# carChargeChannel.net
KiCad netlist of a schematic drawn in EAGLE
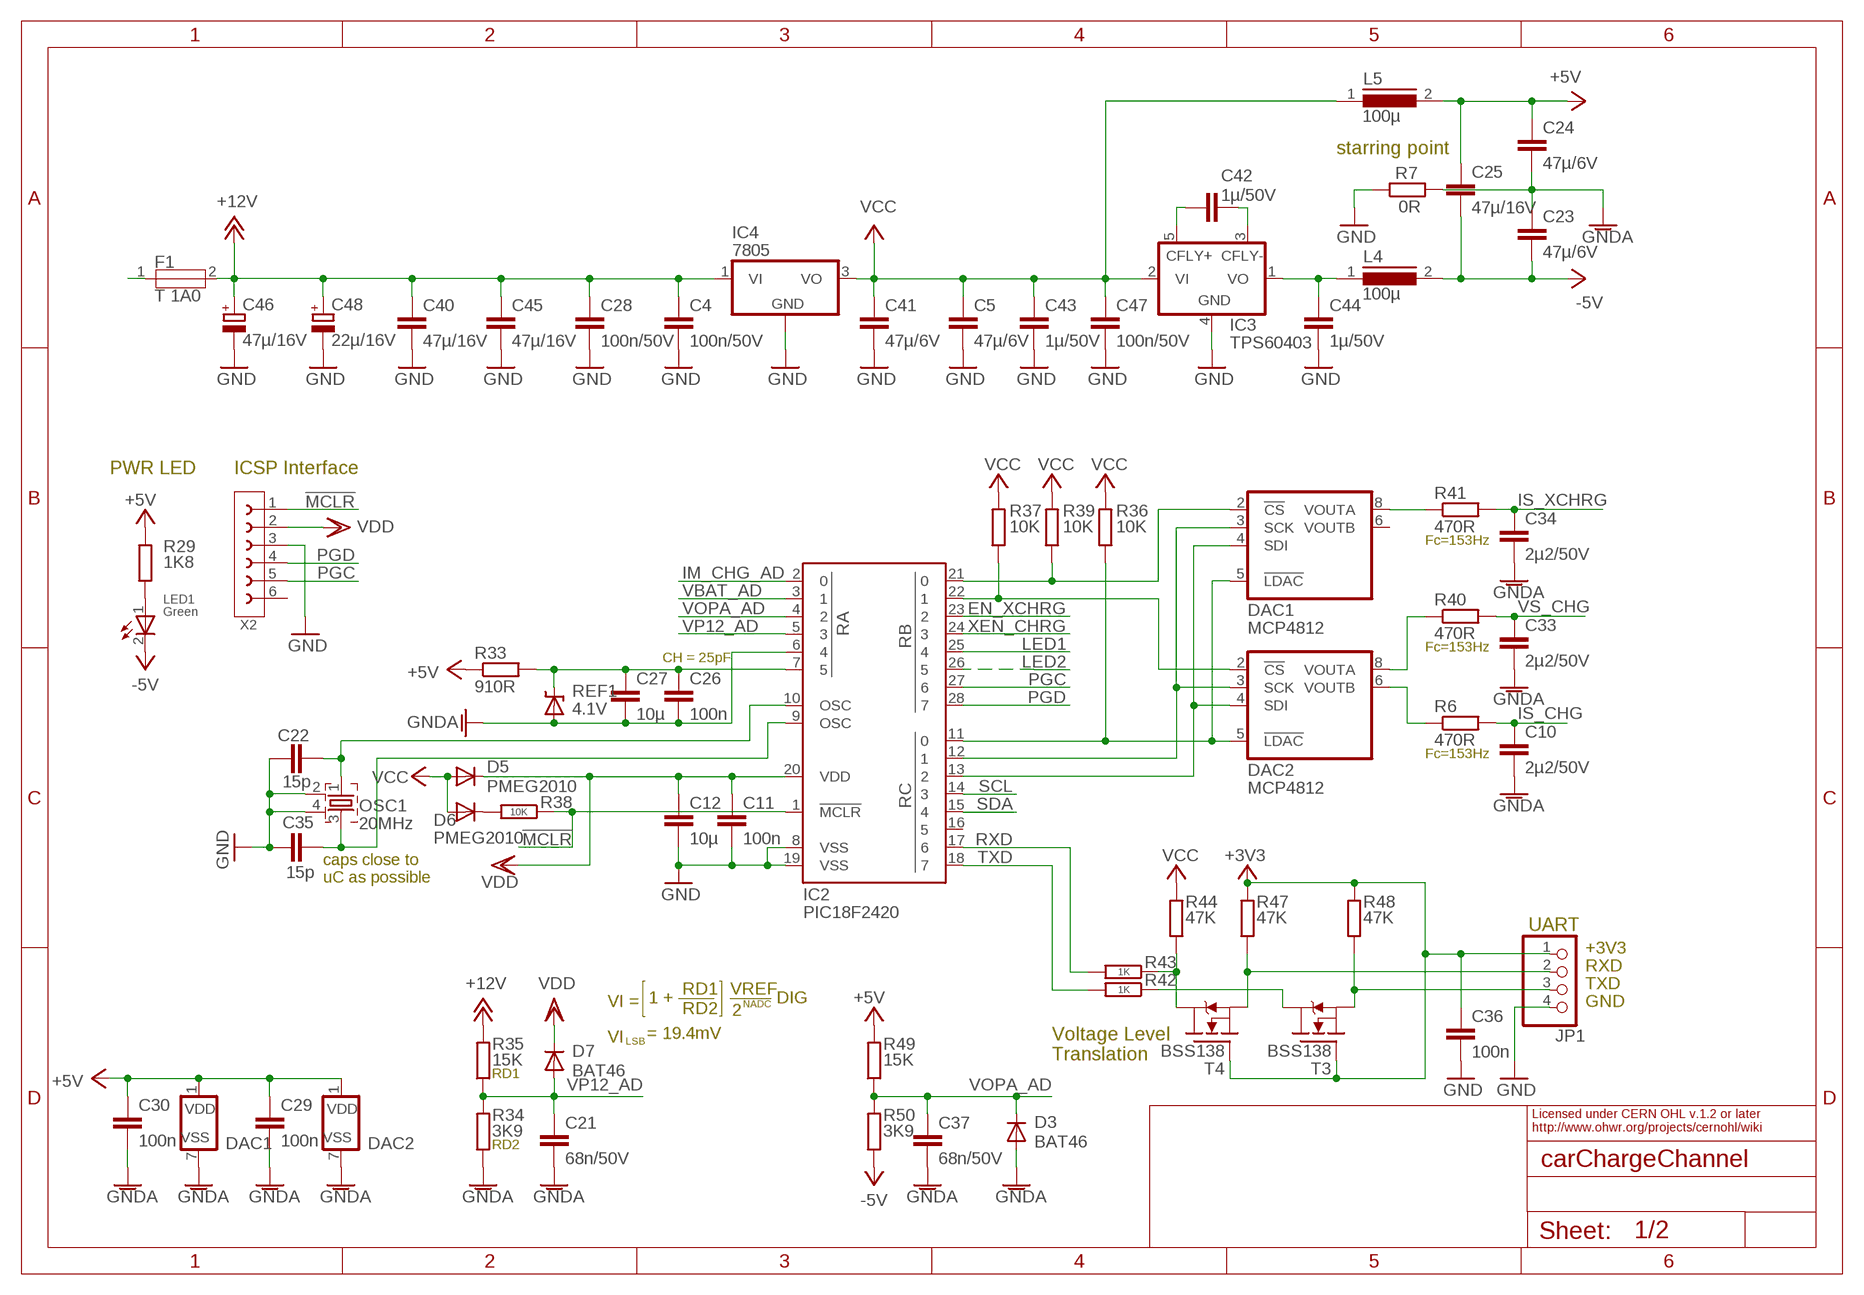
[diagram p0: schematic, sheet 1]
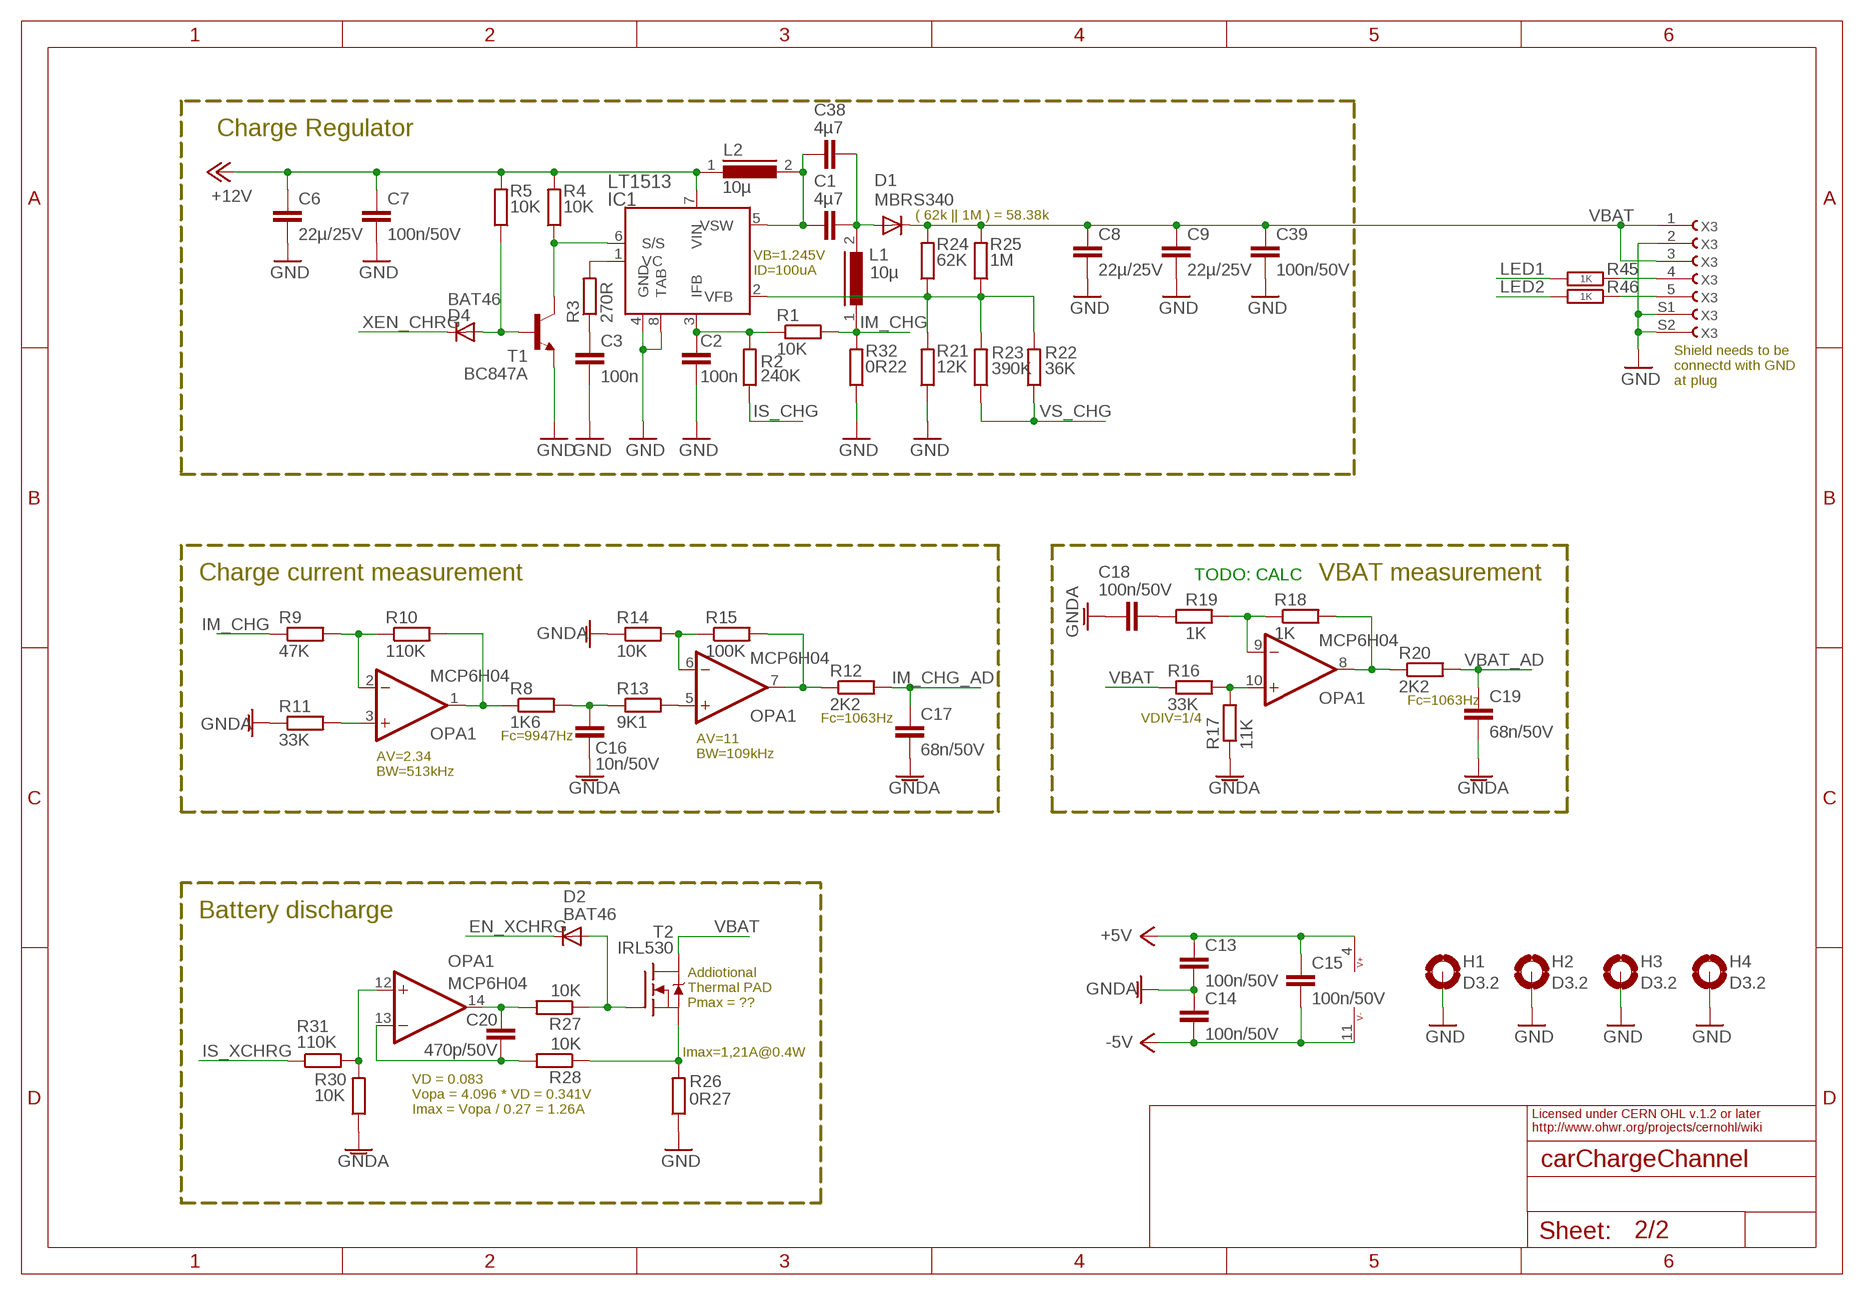
[diagram p1: schematic, sheet 2]

(export (version "E")
  (design (tool "Eeschema 10.0.6"))
  (components
    (comp (ref "C4")
      (value "100n/50V")
      (footprint "eagle-import:1206")
      (libsource (lib "eagle-import") (part "X7R-1206-100000P"))
    )
    (comp (ref "C5")
      (value "47µ/6V")
      (footprint "eagle-import:1206")
      (libsource (lib "eagle-import") (part "X5R-1206-47000000P"))
    )
    (comp (ref "C10")
      (value "2µ2/50V")
      (footprint "eagle-import:1206")
      (libsource (lib "eagle-import") (part "X7R-1206-2200000P"))
    )
    (comp (ref "C11")
      (value "100n")
      (footprint "eagle-import:1206")
      (libsource (lib "eagle-import") (part "X7R-1206-100000P"))
    )
    (comp (ref "C12")
      (value "10µ")
      (footprint "eagle-import:1206")
      (libsource (lib "eagle-import") (part "X7R-1206-10000000P"))
    )
    (comp (ref "C21")
      (value "68n/50V")
      (footprint "eagle-import:1206")
      (libsource (lib "eagle-import") (part "X7R-1206-68000P"))
    )
    (comp (ref "C22")
      (value "15p")
      (footprint "eagle-import:1206")
      (libsource (lib "eagle-import") (part "NP0-1206-15P"))
    )
    (comp (ref "C23")
      (value "47µ/6V")
      (footprint "eagle-import:1206")
      (libsource (lib "eagle-import") (part "X5R-1206-47000000P"))
    )
    (comp (ref "C24")
      (value "47µ/6V")
      (footprint "eagle-import:1206")
      (libsource (lib "eagle-import") (part "X5R-1206-47000000P"))
    )
    (comp (ref "C25")
      (value "47µ/16V")
      (footprint "eagle-import:1210")
      (libsource (lib "eagle-import") (part "X5R-1210-47000000P"))
    )
    (comp (ref "C26")
      (value "100n")
      (footprint "eagle-import:1206")
      (libsource (lib "eagle-import") (part "X7R-1206-100000P"))
    )
    (comp (ref "C27")
      (value "10µ")
      (footprint "eagle-import:1206")
      (libsource (lib "eagle-import") (part "X7R-1206-10000000P"))
    )
    (comp (ref "C28")
      (value "100n/50V")
      (footprint "eagle-import:1206")
      (libsource (lib "eagle-import") (part "X7R-1206-100000P"))
    )
    (comp (ref "C29")
      (value "100n")
      (footprint "eagle-import:1206")
      (libsource (lib "eagle-import") (part "X7R-1206-100000P"))
    )
    (comp (ref "C30")
      (value "100n")
      (footprint "eagle-import:1206")
      (libsource (lib "eagle-import") (part "X7R-1206-100000P"))
    )
    (comp (ref "C33")
      (value "2µ2/50V")
      (footprint "eagle-import:1206")
      (libsource (lib "eagle-import") (part "X7R-1206-2200000P"))
    )
    (comp (ref "C34")
      (value "2µ2/50V")
      (footprint "eagle-import:1206")
      (libsource (lib "eagle-import") (part "X7R-1206-2200000P"))
    )
    (comp (ref "C35")
      (value "15p")
      (footprint "eagle-import:1206")
      (libsource (lib "eagle-import") (part "NP0-1206-15P"))
    )
    (comp (ref "C36")
      (value "100n")
      (footprint "eagle-import:1206")
      (libsource (lib "eagle-import") (part "X7R-1206-100000P"))
    )
    (comp (ref "C37")
      (value "68n/50V")
      (footprint "eagle-import:1206")
      (libsource (lib "eagle-import") (part "X7R-1206-68000P"))
    )
    (comp (ref "C40")
      (value "47µ/16V")
      (footprint "eagle-import:1210")
      (libsource (lib "eagle-import") (part "X5R-1210-47000000P"))
    )
    (comp (ref "C41")
      (value "47µ/6V")
      (footprint "eagle-import:1206")
      (libsource (lib "eagle-import") (part "X5R-1206-47000000P"))
    )
    (comp (ref "C42")
      (value "1µ/50V")
      (footprint "eagle-import:1206")
      (libsource (lib "eagle-import") (part "X7R-1206-1000000P"))
    )
    (comp (ref "C43")
      (value "1µ/50V")
      (footprint "eagle-import:1206")
      (libsource (lib "eagle-import") (part "X7R-1206-1000000P"))
    )
    (comp (ref "C44")
      (value "1µ/50V")
      (footprint "eagle-import:1206")
      (libsource (lib "eagle-import") (part "X7R-1206-1000000P"))
    )
    (comp (ref "C45")
      (value "47µ/16V")
      (footprint "eagle-import:1210")
      (libsource (lib "eagle-import") (part "X5R-1210-47000000P"))
    )
    (comp (ref "C46")
      (value "47µ/16V")
      (footprint "eagle-import:PANC")
      (libsource (lib "eagle-import") (part "AEC-C-47U-16V"))
    )
    (comp (ref "C47")
      (value "100n/50V")
      (footprint "eagle-import:1206")
      (libsource (lib "eagle-import") (part "X7R-1206-100000P"))
    )
    (comp (ref "C48")
      (value "22µ/16V")
      (footprint "eagle-import:PANB")
      (libsource (lib "eagle-import") (part "AEC-B-22U-16V"))
    )
    (comp (ref "D3")
      (value "BAT46")
      (footprint "eagle-import:SOD123")
      (libsource (lib "eagle-import") (part "BAT46W"))
    )
    (comp (ref "D5")
      (value "PMEG2010")
      (footprint "eagle-import:SOD323")
      (libsource (lib "eagle-import") (part "PMEGXX10BEA-20V"))
    )
    (comp (ref "D6")
      (value "PMEG2010")
      (footprint "eagle-import:SOD323")
      (libsource (lib "eagle-import") (part "PMEGXX10BEA-20V"))
    )
    (comp (ref "D7")
      (value "BAT46")
      (footprint "eagle-import:SOD123")
      (libsource (lib "eagle-import") (part "BAT46W"))
    )
    (comp (ref "DAC1")
      (value "MCP4812")
      (footprint "eagle-import:MSOP8")
      (libsource (lib "eagle-import") (part "MCP48-E/MS12"))
    )
    (comp (ref "DAC2")
      (value "MCP4812")
      (footprint "eagle-import:MSOP8")
      (libsource (lib "eagle-import") (part "MCP48-E/MS12"))
    )
    (comp (ref "F1")
      (value "T 1A0")
      (footprint "eagle-import:OMT125")
      (libsource (lib "eagle-import") (part "OMT-125V-T1A0"))
    )
    (comp (ref "IC2")
      (value "PIC18F2420")
      (footprint "eagle-import:SOIC28-7.62")
      (libsource (lib "eagle-import") (part "PIC18F2420/SO"))
    )
    (comp (ref "IC3")
      (value "TPS60403")
      (footprint "eagle-import:SOT23-5")
      (libsource (lib "eagle-import") (part "TPS6040DBVT3"))
    )
    (comp (ref "IC4")
      (value "7805")
      (footprint "eagle-import:TO263")
      (libsource (lib "eagle-import") (part "MC78D2T05"))
    )
    (comp (ref "JP1")
      (value "PINHD-1X4")
      (footprint "eagle-import:1X04")
      (libsource (lib "eagle-import") (part "PINHD-1X4"))
    )
    (comp (ref "L4")
      (value "100µ")
      (footprint "eagle-import:1210")
      (libsource (lib "eagle-import") (part "LQH3C101K"))
    )
    (comp (ref "L5")
      (value "100µ")
      (footprint "eagle-import:1210")
      (libsource (lib "eagle-import") (part "LQH3C101K"))
    )
    (comp (ref "LED1")
      (value "Green")
      (footprint "eagle-import:LED3216")
      (libsource (lib "eagle-import") (part "LEDMONO-KP3216-GREEN"))
    )
    (comp (ref "OSC1")
      (value "20MHz")
      (footprint "eagle-import:MT")
      (libsource (lib "eagle-import") (part "MT-20000"))
    )
    (comp (ref "R6")
      (value "470R")
      (footprint "eagle-import:1206")
      (libsource (lib "eagle-import") (part "RC1206-470"))
    )
    (comp (ref "R7")
      (value "0R")
      (footprint "eagle-import:1206")
      (libsource (lib "eagle-import") (part "R1206-1%-0.0"))
    )
    (comp (ref "R29")
      (value "1K8")
      (footprint "eagle-import:1206")
      (libsource (lib "eagle-import") (part "R1206-1%-1800"))
    )
    (comp (ref "R33")
      (value "910R")
      (footprint "eagle-import:1206")
      (libsource (lib "eagle-import") (part "R1206-1%-910"))
    )
    (comp (ref "R34")
      (value "3K9")
      (footprint "eagle-import:1206")
      (libsource (lib "eagle-import") (part "R1206-1%-3900"))
    )
    (comp (ref "R35")
      (value "15K")
      (footprint "eagle-import:1206")
      (libsource (lib "eagle-import") (part "R1206-1%-15000"))
    )
    (comp (ref "R36")
      (value "10K")
      (footprint "eagle-import:1206")
      (libsource (lib "eagle-import") (part "R1206-1%-10000"))
    )
    (comp (ref "R37")
      (value "10K")
      (footprint "eagle-import:1206")
      (libsource (lib "eagle-import") (part "R1206-1%-10000"))
    )
    (comp (ref "R38")
      (value "10K")
      (footprint "eagle-import:1206")
      (libsource (lib "eagle-import") (part "R1206-1%-10000"))
    )
    (comp (ref "R39")
      (value "10K")
      (footprint "eagle-import:1206")
      (libsource (lib "eagle-import") (part "R1206-1%-10000"))
    )
    (comp (ref "R40")
      (value "470R")
      (footprint "eagle-import:1206")
      (libsource (lib "eagle-import") (part "RC1206-470"))
    )
    (comp (ref "R41")
      (value "470R")
      (footprint "eagle-import:1206")
      (libsource (lib "eagle-import") (part "RC1206-470"))
    )
    (comp (ref "R42")
      (value "1K")
      (footprint "eagle-import:1206")
      (libsource (lib "eagle-import") (part "R1206-1%-1000"))
    )
    (comp (ref "R43")
      (value "1K")
      (footprint "eagle-import:1206")
      (libsource (lib "eagle-import") (part "R1206-1%-1000"))
    )
    (comp (ref "R44")
      (value "47K")
      (footprint "eagle-import:1206")
      (libsource (lib "eagle-import") (part "R1206-1%-47000"))
    )
    (comp (ref "R47")
      (value "47K")
      (footprint "eagle-import:1206")
      (libsource (lib "eagle-import") (part "R1206-1%-47000"))
    )
    (comp (ref "R48")
      (value "47K")
      (footprint "eagle-import:1206")
      (libsource (lib "eagle-import") (part "R1206-1%-47000"))
    )
    (comp (ref "R49")
      (value "15K")
      (footprint "eagle-import:1206")
      (libsource (lib "eagle-import") (part "R1206-1%-15000"))
    )
    (comp (ref "R50")
      (value "3K9")
      (footprint "eagle-import:1206")
      (libsource (lib "eagle-import") (part "R1206-1%-3900"))
    )
    (comp (ref "REF1")
      (value "4.1V")
      (footprint "eagle-import:SOT23")
      (libsource (lib "eagle-import") (part "LM4040-MF03A-4.1V"))
    )
    (comp (ref "T3")
      (value "BSS138")
      (footprint "eagle-import:SOT23")
      (libsource (lib "eagle-import") (part "BSS138"))
    )
    (comp (ref "T4")
      (value "BSS138")
      (footprint "eagle-import:SOT23")
      (libsource (lib "eagle-import") (part "BSS138"))
    )
    (comp (ref "X2")
      (value "2X3")
      (footprint "eagle-import:BOXHD-06-2.54-S")
      (libsource (lib "eagle-import") (part "BOXHD-06-2.54-S"))
    )
    (comp (ref "C1")
      (value "4µ7")
      (footprint "eagle-import:1206")
      (libsource (lib "eagle-import") (part "X7R-1206-4700000P"))
    )
    (comp (ref "C2")
      (value "100n")
      (footprint "eagle-import:1206")
      (libsource (lib "eagle-import") (part "X7R-1206-100000P"))
    )
    (comp (ref "C3")
      (value "100n")
      (footprint "eagle-import:1206")
      (libsource (lib "eagle-import") (part "X7R-1206-100000P"))
    )
    (comp (ref "C6")
      (value "22µ/25V")
      (footprint "eagle-import:1210")
      (libsource (lib "eagle-import") (part "X5R-1210-22000000P"))
    )
    (comp (ref "C7")
      (value "100n/50V")
      (footprint "eagle-import:1206")
      (libsource (lib "eagle-import") (part "X7R-1206-100000P"))
    )
    (comp (ref "C8")
      (value "22µ/25V")
      (footprint "eagle-import:1210")
      (libsource (lib "eagle-import") (part "X5R-1210-22000000P"))
    )
    (comp (ref "C9")
      (value "22µ/25V")
      (footprint "eagle-import:1210")
      (libsource (lib "eagle-import") (part "X5R-1210-22000000P"))
    )
    (comp (ref "C13")
      (value "100n/50V")
      (footprint "eagle-import:1206")
      (libsource (lib "eagle-import") (part "X7R-1206-100000P"))
    )
    (comp (ref "C14")
      (value "100n/50V")
      (footprint "eagle-import:1206")
      (libsource (lib "eagle-import") (part "X7R-1206-100000P"))
    )
    (comp (ref "C15")
      (value "100n/50V")
      (footprint "eagle-import:1206")
      (libsource (lib "eagle-import") (part "X7R-1206-100000P"))
    )
    (comp (ref "C16")
      (value "10n/50V")
      (footprint "eagle-import:1206")
      (libsource (lib "eagle-import") (part "X7R-1206-10000P"))
    )
    (comp (ref "C17")
      (value "68n/50V")
      (footprint "eagle-import:1206")
      (libsource (lib "eagle-import") (part "X7R-1206-68000P"))
    )
    (comp (ref "C18")
      (value "100n/50V")
      (footprint "eagle-import:1206")
      (libsource (lib "eagle-import") (part "X7R-1206-100000P"))
    )
    (comp (ref "C19")
      (value "68n/50V")
      (footprint "eagle-import:1206")
      (libsource (lib "eagle-import") (part "X7R-1206-68000P"))
    )
    (comp (ref "C20")
      (value "470p/50V")
      (footprint "eagle-import:1206")
      (libsource (lib "eagle-import") (part "NP0-1206-470P"))
    )
    (comp (ref "C38")
      (value "4µ7")
      (footprint "eagle-import:1206")
      (libsource (lib "eagle-import") (part "X7R-1206-4700000P"))
    )
    (comp (ref "C39")
      (value "100n/50V")
      (footprint "eagle-import:1206")
      (libsource (lib "eagle-import") (part "X7R-1206-100000P"))
    )
    (comp (ref "D1")
      (value "MBRS340")
      (footprint "eagle-import:DO214AB")
      (libsource (lib "eagle-import") (part "MBRS340"))
    )
    (comp (ref "D2")
      (value "BAT46")
      (footprint "eagle-import:SOD123")
      (libsource (lib "eagle-import") (part "BAT46W"))
    )
    (comp (ref "D4")
      (value "BAT46")
      (footprint "eagle-import:SOD123")
      (libsource (lib "eagle-import") (part "BAT46W"))
    )
    (comp (ref "H1")
      (value "D3.2")
      (footprint "eagle-import:3,2-PAD")
      (libsource (lib "eagle-import") (part "MOUNT-PAD-ROUND3.2"))
    )
    (comp (ref "H2")
      (value "D3.2")
      (footprint "eagle-import:3,2-PAD")
      (libsource (lib "eagle-import") (part "MOUNT-PAD-ROUND3.2"))
    )
    (comp (ref "H3")
      (value "D3.2")
      (footprint "eagle-import:3,2-PAD")
      (libsource (lib "eagle-import") (part "MOUNT-PAD-ROUND3.2"))
    )
    (comp (ref "H4")
      (value "D3.2")
      (footprint "eagle-import:3,2-PAD")
      (libsource (lib "eagle-import") (part "MOUNT-PAD-ROUND3.2"))
    )
    (comp (ref "IC1")
      (value "LT1513")
      (footprint "eagle-import:TO263-7")
      (libsource (lib "eagle-import") (part "LT1513CR"))
    )
    (comp (ref "L1")
      (value "10µ")
      (footprint "eagle-import:DR74")
      (libsource (lib "eagle-import") (part "DR--7410U"))
    )
    (comp (ref "L2")
      (value "10µ")
      (footprint "eagle-import:DR74")
      (libsource (lib "eagle-import") (part "DR--7410U"))
    )
    (comp (ref "OPA1")
      (value "MCP6H04")
      (footprint "eagle-import:SOIC14")
      (libsource (lib "eagle-import") (part "MCP6H04"))
    )
    (comp (ref "R1")
      (value "10K")
      (footprint "eagle-import:1206")
      (libsource (lib "eagle-import") (part "R1206-1%-10000"))
    )
    (comp (ref "R2")
      (value "240K")
      (footprint "eagle-import:1206")
      (libsource (lib "eagle-import") (part "R1206-1%-240000"))
    )
    (comp (ref "R3")
      (value "270R")
      (footprint "eagle-import:1206")
      (libsource (lib "eagle-import") (part "R1206-1%-270"))
    )
    (comp (ref "R4")
      (value "10K")
      (footprint "eagle-import:1206")
      (libsource (lib "eagle-import") (part "R1206-1%-10000"))
    )
    (comp (ref "R5")
      (value "10K")
      (footprint "eagle-import:1206")
      (libsource (lib "eagle-import") (part "R1206-1%-10000"))
    )
    (comp (ref "R8")
      (value "1K6")
      (footprint "eagle-import:1206")
      (libsource (lib "eagle-import") (part "R1206-1%-1600"))
    )
    (comp (ref "R9")
      (value "47K")
      (footprint "eagle-import:1206")
      (libsource (lib "eagle-import") (part "R1206-1%-47000"))
    )
    (comp (ref "R10")
      (value "110K")
      (footprint "eagle-import:1206")
      (libsource (lib "eagle-import") (part "R1206-1%-110000"))
    )
    (comp (ref "R11")
      (value "33K")
      (footprint "eagle-import:1206")
      (libsource (lib "eagle-import") (part "R1206-1%-33000"))
    )
    (comp (ref "R12")
      (value "2K2")
      (footprint "eagle-import:1206")
      (libsource (lib "eagle-import") (part "R1206-1%-2200"))
    )
    (comp (ref "R13")
      (value "9K1")
      (footprint "eagle-import:1206")
      (libsource (lib "eagle-import") (part "R1206-1%-9100"))
    )
    (comp (ref "R14")
      (value "10K")
      (footprint "eagle-import:1206")
      (libsource (lib "eagle-import") (part "R1206-1%-10000"))
    )
    (comp (ref "R15")
      (value "100K")
      (footprint "eagle-import:1206")
      (libsource (lib "eagle-import") (part "R1206-1%-100000"))
    )
    (comp (ref "R16")
      (value "33K")
      (footprint "eagle-import:1206")
      (libsource (lib "eagle-import") (part "R1206-1%-33000"))
    )
    (comp (ref "R17")
      (value "11K")
      (footprint "eagle-import:1206")
      (libsource (lib "eagle-import") (part "R1206-1%-11000"))
    )
    (comp (ref "R18")
      (value "1K")
      (footprint "eagle-import:1206")
      (libsource (lib "eagle-import") (part "R1206-1%-1000"))
    )
    (comp (ref "R19")
      (value "1K")
      (footprint "eagle-import:1206")
      (libsource (lib "eagle-import") (part "R1206-1%-1000"))
    )
    (comp (ref "R20")
      (value "2K2")
      (footprint "eagle-import:1206")
      (libsource (lib "eagle-import") (part "R1206-1%-2200"))
    )
    (comp (ref "R21")
      (value "12K")
      (footprint "eagle-import:1206")
      (libsource (lib "eagle-import") (part "R1206-1%-12000"))
    )
    (comp (ref "R22")
      (value "36K")
      (footprint "eagle-import:1206")
      (libsource (lib "eagle-import") (part "R1206-1%-36000"))
    )
    (comp (ref "R23")
      (value "390K")
      (footprint "eagle-import:1206")
      (libsource (lib "eagle-import") (part "R1206-1%-390000"))
    )
    (comp (ref "R24")
      (value "62K")
      (footprint "eagle-import:1206")
      (libsource (lib "eagle-import") (part "R1206-1%-62000"))
    )
    (comp (ref "R25")
      (value "1M")
      (footprint "eagle-import:1206")
      (libsource (lib "eagle-import") (part "R1206-1%-1000000"))
    )
    (comp (ref "R26")
      (value "0R27")
      (footprint "eagle-import:1206")
      (libsource (lib "eagle-import") (part "R1206-5%-0.27"))
    )
    (comp (ref "R27")
      (value "10K")
      (footprint "eagle-import:1206")
      (libsource (lib "eagle-import") (part "R1206-1%-10000"))
    )
    (comp (ref "R28")
      (value "10K")
      (footprint "eagle-import:1206")
      (libsource (lib "eagle-import") (part "R1206-1%-10000"))
    )
    (comp (ref "R30")
      (value "10K")
      (footprint "eagle-import:1206")
      (libsource (lib "eagle-import") (part "R1206-1%-10000"))
    )
    (comp (ref "R31")
      (value "110K")
      (footprint "eagle-import:1206")
      (libsource (lib "eagle-import") (part "R1206-1%-110000"))
    )
    (comp (ref "R32")
      (value "0R22")
      (footprint "eagle-import:1206")
      (libsource (lib "eagle-import") (part "R1206-1%-0.22"))
    )
    (comp (ref "R45")
      (value "1K")
      (footprint "eagle-import:1206")
      (libsource (lib "eagle-import") (part "R1206-1%-1000"))
    )
    (comp (ref "R46")
      (value "1K")
      (footprint "eagle-import:1206")
      (libsource (lib "eagle-import") (part "R1206-1%-1000"))
    )
    (comp (ref "T1")
      (value "BC847A")
      (footprint "eagle-import:SOT23")
      (libsource (lib "eagle-import") (part "BC847A"))
    )
    (comp (ref "T2")
      (value "IRL530")
      (footprint "eagle-import:TO263AB")
      (libsource (lib "eagle-import") (part "IRL530NS"))
    )
    (comp (ref "X3")
      (value "DIN5")
      (footprint "eagle-import:DIN5P")
      (libsource (lib "eagle-import") (part "MAB-5S"))
    )
  )
  (nets
    (net (code "1") (name "+3V3") (class "Default")
      (node (ref "C36") (pin "1") (pinfunction "1_1") (pintype "passive"))
      (node (ref "JP1") (pin "1") (pinfunction "1_1") (pintype "passive"))
      (node (ref "R47") (pin "2") (pinfunction "2_2") (pintype "passive"))
      (node (ref "R48") (pin "2") (pinfunction "2_2") (pintype "passive"))
      (node (ref "T3") (pin "1") (pinfunction "G_1") (pintype "bidirectional"))
      (node (ref "T4") (pin "1") (pinfunction "G_1") (pintype "bidirectional"))
    )
    (net (code "2") (name "+5V") (class "Default")
      (node (ref "C13") (pin "1") (pinfunction "1_1") (pintype "passive"))
      (node (ref "C15") (pin "1") (pinfunction "1_1") (pintype "passive"))
      (node (ref "C24") (pin "1") (pinfunction "1_1") (pintype "passive"))
      (node (ref "C25") (pin "1") (pinfunction "1_1") (pintype "passive"))
      (node (ref "C29") (pin "1") (pinfunction "1_1") (pintype "passive"))
      (node (ref "C30") (pin "1") (pinfunction "1_1") (pintype "passive"))
      (node (ref "DAC1") (pin "1") (pinfunction "VDD_1") (pintype "power_in"))
      (node (ref "DAC2") (pin "1") (pinfunction "VDD_1") (pintype "power_in"))
      (node (ref "L5") (pin "2") (pinfunction "2_2") (pintype "passive"))
      (node (ref "OPA1") (pin "4") (pinfunction "V+_4") (pintype "power_in"))
      (node (ref "R29") (pin "2") (pinfunction "2_2") (pintype "passive"))
      (node (ref "R33") (pin "1") (pinfunction "1_1") (pintype "passive"))
      (node (ref "R49") (pin "2") (pinfunction "2_2") (pintype "passive"))
    )
    (net (code "3") (name "+12V") (class "Default")
      (node (ref "C28") (pin "1") (pinfunction "1_1") (pintype "passive"))
      (node (ref "C4") (pin "1") (pinfunction "1_1") (pintype "passive"))
      (node (ref "C40") (pin "1") (pinfunction "1_1") (pintype "passive"))
      (node (ref "C45") (pin "1") (pinfunction "1_1") (pintype "passive"))
      (node (ref "C46") (pin "CP") (pinfunction "+_CP") (pintype "passive"))
      (node (ref "C48") (pin "CP") (pinfunction "+_CP") (pintype "passive"))
      (node (ref "C6") (pin "1") (pinfunction "1_1") (pintype "passive"))
      (node (ref "C7") (pin "1") (pinfunction "1_1") (pintype "passive"))
      (node (ref "F1") (pin "2") (pinfunction "P$2_2") (pintype "passive"))
      (node (ref "IC1") (pin "7") (pinfunction "VIN_7") (pintype "input"))
      (node (ref "IC4") (pin "1") (pinfunction "VI_1") (pintype "input"))
      (node (ref "L2") (pin "1") (pinfunction "1_1") (pintype "passive"))
      (node (ref "R35") (pin "2") (pinfunction "2_2") (pintype "passive"))
      (node (ref "R4") (pin "2") (pinfunction "2_2") (pintype "passive"))
      (node (ref "R5") (pin "2") (pinfunction "2_2") (pintype "passive"))
    )
    (net (code "4") (name "-5V") (class "Default")
      (node (ref "C14") (pin "2") (pinfunction "2_2") (pintype "passive"))
      (node (ref "C15") (pin "2") (pinfunction "2_2") (pintype "passive"))
      (node (ref "C23") (pin "2") (pinfunction "2_2") (pintype "passive"))
      (node (ref "C25") (pin "2") (pinfunction "2_2") (pintype "passive"))
      (node (ref "L4") (pin "2") (pinfunction "2_2") (pintype "passive"))
      (node (ref "LED1") (pin "2") (pinfunction "C_2") (pintype "passive"))
      (node (ref "OPA1") (pin "11") (pinfunction "V-_11") (pintype "power_in"))
      (node (ref "R50") (pin "1") (pinfunction "1_1") (pintype "passive"))
    )
    (net (code "5") (name "EN_XCHRG") (class "Default")
      (node (ref "D2") (pin "C") (pinfunction "C_C") (pintype "passive"))
      (node (ref "IC2") (pin "23") (pinfunction "2_23") (pintype "bidirectional"))
    )
    (net (code "6") (name "GND") (class "Default")
      (node (ref "C11") (pin "2") (pinfunction "2_2") (pintype "passive"))
      (node (ref "C12") (pin "2") (pinfunction "2_2") (pintype "passive"))
      (node (ref "C2") (pin "2") (pinfunction "2_2") (pintype "passive"))
      (node (ref "C22") (pin "2") (pinfunction "2_2") (pintype "passive"))
      (node (ref "C28") (pin "2") (pinfunction "2_2") (pintype "passive"))
      (node (ref "C3") (pin "2") (pinfunction "2_2") (pintype "passive"))
      (node (ref "C35") (pin "2") (pinfunction "2_2") (pintype "passive"))
      (node (ref "C36") (pin "2") (pinfunction "2_2") (pintype "passive"))
      (node (ref "C39") (pin "2") (pinfunction "2_2") (pintype "passive"))
      (node (ref "C4") (pin "2") (pinfunction "2_2") (pintype "passive"))
      (node (ref "C40") (pin "2") (pinfunction "2_2") (pintype "passive"))
      (node (ref "C41") (pin "2") (pinfunction "2_2") (pintype "passive"))
      (node (ref "C43") (pin "2") (pinfunction "2_2") (pintype "passive"))
      (node (ref "C44") (pin "2") (pinfunction "2_2") (pintype "passive"))
      (node (ref "C45") (pin "2") (pinfunction "2_2") (pintype "passive"))
      (node (ref "C46") (pin "CN") (pinfunction "-_CN") (pintype "passive"))
      (node (ref "C47") (pin "2") (pinfunction "2_2") (pintype "passive"))
      (node (ref "C48") (pin "CN") (pinfunction "-_CN") (pintype "passive"))
      (node (ref "C5") (pin "2") (pinfunction "2_2") (pintype "passive"))
      (node (ref "C6") (pin "2") (pinfunction "2_2") (pintype "passive"))
      (node (ref "C7") (pin "2") (pinfunction "2_2") (pintype "passive"))
      (node (ref "C8") (pin "2") (pinfunction "2_2") (pintype "passive"))
      (node (ref "C9") (pin "2") (pinfunction "2_2") (pintype "passive"))
      (node (ref "H1") (pin "B3,2") (pinfunction "MOUNT_B3,2") (pintype "passive"))
      (node (ref "H2") (pin "B3,2") (pinfunction "MOUNT_B3,2") (pintype "passive"))
      (node (ref "H3") (pin "B3,2") (pinfunction "MOUNT_B3,2") (pintype "passive"))
      (node (ref "H4") (pin "B3,2") (pinfunction "MOUNT_B3,2") (pintype "passive"))
      (node (ref "IC1") (pin "4") (pinfunction "GND_4") (pintype "power_in"))
      (node (ref "IC1") (pin "8") (pinfunction "TAB_8") (pintype "power_in"))
      (node (ref "IC2") (pin "19") (pinfunction "VSS_19") (pintype "power_in"))
      (node (ref "IC2") (pin "8") (pinfunction "VSS_8") (pintype "power_in"))
      (node (ref "IC3") (pin "4") (pinfunction "GND_4") (pintype "power_in"))
      (node (ref "IC4") (pin "4") (pinfunction "GND_4") (pintype "power_in"))
      (node (ref "JP1") (pin "4") (pinfunction "4_4") (pintype "passive"))
      (node (ref "OSC1") (pin "2") (pinfunction "2_2") (pintype "passive"))
      (node (ref "OSC1") (pin "4") (pinfunction "4_4") (pintype "passive"))
      (node (ref "R21") (pin "1") (pinfunction "1_1") (pintype "passive"))
      (node (ref "R26") (pin "1") (pinfunction "1_1") (pintype "passive"))
      (node (ref "R32") (pin "1") (pinfunction "1_1") (pintype "passive"))
      (node (ref "R7") (pin "1") (pinfunction "1_1") (pintype "passive"))
      (node (ref "T1") (pin "2") (pinfunction "E_2") (pintype "passive"))
      (node (ref "X2") (pin "3") (pinfunction "P$1_3") (pintype "bidirectional"))
      (node (ref "X3") (pin "2") (pinfunction "P$1_2") (pintype "bidirectional"))
      (node (ref "X3") (pin "S1") (pinfunction "P$1_S1") (pintype "bidirectional"))
      (node (ref "X3") (pin "S2") (pinfunction "P$1_S2") (pintype "bidirectional"))
    )
    (net (code "7") (name "GNDA") (class "Default")
      (node (ref "C10") (pin "2") (pinfunction "2_2") (pintype "passive"))
      (node (ref "C13") (pin "2") (pinfunction "2_2") (pintype "passive"))
      (node (ref "C14") (pin "1") (pinfunction "1_1") (pintype "passive"))
      (node (ref "C16") (pin "2") (pinfunction "2_2") (pintype "passive"))
      (node (ref "C17") (pin "2") (pinfunction "2_2") (pintype "passive"))
      (node (ref "C18") (pin "1") (pinfunction "1_1") (pintype "passive"))
      (node (ref "C19") (pin "2") (pinfunction "2_2") (pintype "passive"))
      (node (ref "C21") (pin "2") (pinfunction "2_2") (pintype "passive"))
      (node (ref "C23") (pin "1") (pinfunction "1_1") (pintype "passive"))
      (node (ref "C24") (pin "2") (pinfunction "2_2") (pintype "passive"))
      (node (ref "C26") (pin "2") (pinfunction "2_2") (pintype "passive"))
      (node (ref "C27") (pin "2") (pinfunction "2_2") (pintype "passive"))
      (node (ref "C29") (pin "2") (pinfunction "2_2") (pintype "passive"))
      (node (ref "C30") (pin "2") (pinfunction "2_2") (pintype "passive"))
      (node (ref "C33") (pin "2") (pinfunction "2_2") (pintype "passive"))
      (node (ref "C34") (pin "2") (pinfunction "2_2") (pintype "passive"))
      (node (ref "C37") (pin "2") (pinfunction "2_2") (pintype "passive"))
      (node (ref "D3") (pin "A") (pinfunction "A_A") (pintype "passive"))
      (node (ref "DAC1") (pin "7") (pinfunction "VSS_7") (pintype "power_in"))
      (node (ref "DAC2") (pin "7") (pinfunction "VSS_7") (pintype "power_in"))
      (node (ref "IC2") (pin "6") (pinfunction "4_6") (pintype "bidirectional"))
      (node (ref "R11") (pin "1") (pinfunction "1_1") (pintype "passive"))
      (node (ref "R14") (pin "1") (pinfunction "1_1") (pintype "passive"))
      (node (ref "R17") (pin "1") (pinfunction "1_1") (pintype "passive"))
      (node (ref "R30") (pin "1") (pinfunction "1_1") (pintype "passive"))
      (node (ref "R34") (pin "1") (pinfunction "1_1") (pintype "passive"))
      (node (ref "R7") (pin "2") (pinfunction "2_2") (pintype "passive"))
      (node (ref "REF1") (pin "1") (pinfunction "A_1") (pintype "passive"))
    )
    (net (code "8") (name "IM_CHG") (class "Default")
      (node (ref "L1") (pin "1") (pinfunction "1_1") (pintype "passive"))
      (node (ref "R1") (pin "2") (pinfunction "2_2") (pintype "passive"))
      (node (ref "R32") (pin "2") (pinfunction "2_2") (pintype "passive"))
      (node (ref "R9") (pin "1") (pinfunction "1_1") (pintype "passive"))
    )
    (net (code "9") (name "IM_CHG_AD") (class "Default")
      (node (ref "C17") (pin "1") (pinfunction "1_1") (pintype "passive"))
      (node (ref "IC2") (pin "2") (pinfunction "0_2") (pintype "bidirectional"))
      (node (ref "R12") (pin "2") (pinfunction "2_2") (pintype "passive"))
    )
    (net (code "10") (name "IS_CHG") (class "Default")
      (node (ref "C10") (pin "1") (pinfunction "1_1") (pintype "passive"))
      (node (ref "R2") (pin "1") (pinfunction "1_1") (pintype "passive"))
      (node (ref "R6") (pin "2") (pinfunction "2_2") (pintype "passive"))
    )
    (net (code "11") (name "IS_XCHRG") (class "Default")
      (node (ref "C34") (pin "1") (pinfunction "1_1") (pintype "passive"))
      (node (ref "R31") (pin "1") (pinfunction "1_1") (pintype "passive"))
      (node (ref "R41") (pin "2") (pinfunction "2_2") (pintype "passive"))
    )
    (net (code "12") (name "LED1") (class "Default")
      (node (ref "IC2") (pin "25") (pinfunction "4_25") (pintype "bidirectional"))
      (node (ref "R45") (pin "2") (pinfunction "2_2") (pintype "passive"))
    )
    (net (code "13") (name "LED2") (class "Default")
      (node (ref "IC2") (pin "26") (pinfunction "5_26") (pintype "bidirectional"))
      (node (ref "R46") (pin "2") (pinfunction "2_2") (pintype "passive"))
    )
    (net (code "14") (name "Net-(C1-Pad2)") (class "Default")
      (node (ref "C1") (pin "2") (pinfunction "2_2") (pintype "passive"))
      (node (ref "C38") (pin "2") (pinfunction "2_2") (pintype "passive"))
      (node (ref "D1") (pin "A") (pinfunction "A_A") (pintype "passive"))
      (node (ref "L1") (pin "2") (pinfunction "2_2") (pintype "passive"))
    )
    (net (code "15") (name "Net-(C3-Pad1)") (class "Default")
      (node (ref "C3") (pin "1") (pinfunction "1_1") (pintype "passive"))
      (node (ref "R3") (pin "1") (pinfunction "1_1") (pintype "passive"))
    )
    (net (code "16") (name "Net-(C16-Pad1)") (class "Default")
      (node (ref "C16") (pin "1") (pinfunction "1_1") (pintype "passive"))
      (node (ref "R13") (pin "1") (pinfunction "1_1") (pintype "passive"))
      (node (ref "R8") (pin "2") (pinfunction "2_2") (pintype "passive"))
    )
    (net (code "17") (name "Net-(C18-Pad2)") (class "Default")
      (node (ref "C18") (pin "2") (pinfunction "2_2") (pintype "passive"))
      (node (ref "R19") (pin "1") (pinfunction "1_1") (pintype "passive"))
    )
    (net (code "18") (name "Net-(C22-Pad1)") (class "Default")
      (node (ref "C22") (pin "1") (pinfunction "1_1") (pintype "passive"))
      (node (ref "IC2") (pin "10") (pinfunction "OSC_10") (pintype "bidirectional"))
      (node (ref "OSC1") (pin "1") (pinfunction "1_1") (pintype "passive"))
    )
    (net (code "19") (name "Net-(C35-Pad1)") (class "Default")
      (node (ref "C35") (pin "1") (pinfunction "1_1") (pintype "passive"))
      (node (ref "IC2") (pin "9") (pinfunction "OSC_9") (pintype "bidirectional"))
      (node (ref "OSC1") (pin "3") (pinfunction "3_3") (pintype "passive"))
    )
    (net (code "20") (name "Net-(D6-PadC)") (class "Default")
      (node (ref "D6") (pin "C") (pinfunction "C_C") (pintype "passive"))
      (node (ref "R38") (pin "2") (pinfunction "2_2") (pintype "passive"))
    )
    (net (code "21") (name "Net-(DAC1A-SCK)") (class "Default")
      (node (ref "DAC1") (pin "3") (pinfunction "SCK_3") (pintype "input"))
      (node (ref "DAC2") (pin "3") (pinfunction "SCK_3") (pintype "input"))
      (node (ref "IC2") (pin "12") (pinfunction "1_12") (pintype "bidirectional"))
    )
    (net (code "22") (name "Net-(DAC1A-SDI)") (class "Default")
      (node (ref "DAC1") (pin "4") (pinfunction "SDI_4") (pintype "input"))
      (node (ref "DAC2") (pin "4") (pinfunction "SDI_4") (pintype "input"))
      (node (ref "IC2") (pin "13") (pinfunction "2_13") (pintype "bidirectional"))
    )
    (net (code "23") (name "Net-(DAC1A-VOUTA)") (class "Default")
      (node (ref "DAC1") (pin "8") (pinfunction "VOUTA_8") (pintype "bidirectional"))
      (node (ref "R41") (pin "1") (pinfunction "1_1") (pintype "passive"))
    )
    (net (code "24") (name "Net-(DAC1A-~{CS})") (class "Default")
      (node (ref "DAC1") (pin "2") (pinfunction "~{CS}_2") (pintype "input"))
      (node (ref "IC2") (pin "21") (pinfunction "0_21") (pintype "bidirectional"))
      (node (ref "R39") (pin "1") (pinfunction "1_1") (pintype "passive"))
    )
    (net (code "25") (name "Net-(DAC1A-~{LDAC})") (class "Default")
      (node (ref "DAC1") (pin "5") (pinfunction "~{LDAC}_5") (pintype "input"))
      (node (ref "DAC2") (pin "5") (pinfunction "~{LDAC}_5") (pintype "input"))
      (node (ref "IC2") (pin "11") (pinfunction "0_11") (pintype "bidirectional"))
      (node (ref "R36") (pin "1") (pinfunction "1_1") (pintype "passive"))
    )
    (net (code "26") (name "Net-(DAC2A-VOUTA)") (class "Default")
      (node (ref "DAC2") (pin "8") (pinfunction "VOUTA_8") (pintype "bidirectional"))
      (node (ref "R40") (pin "1") (pinfunction "1_1") (pintype "passive"))
    )
    (net (code "27") (name "Net-(DAC2A-VOUTB)") (class "Default")
      (node (ref "DAC2") (pin "6") (pinfunction "VOUTB_6") (pintype "bidirectional"))
      (node (ref "R6") (pin "1") (pinfunction "1_1") (pintype "passive"))
    )
    (net (code "28") (name "Net-(DAC2A-~{CS})") (class "Default")
      (node (ref "DAC2") (pin "2") (pinfunction "~{CS}_2") (pintype "input"))
      (node (ref "IC2") (pin "22") (pinfunction "1_22") (pintype "bidirectional"))
      (node (ref "R37") (pin "1") (pinfunction "1_1") (pintype "passive"))
    )
    (net (code "29") (name "Net-(IC1-IFB)") (class "Default")
      (node (ref "C2") (pin "1") (pinfunction "1_1") (pintype "passive"))
      (node (ref "IC1") (pin "3") (pinfunction "IFB_3") (pintype "passive"))
      (node (ref "R1") (pin "1") (pinfunction "1_1") (pintype "passive"))
      (node (ref "R2") (pin "2") (pinfunction "2_2") (pintype "passive"))
    )
    (net (code "30") (name "Net-(IC1-S{slash}S)") (class "Default")
      (node (ref "IC1") (pin "6") (pinfunction "S/S_6") (pintype "passive"))
      (node (ref "R4") (pin "1") (pinfunction "1_1") (pintype "passive"))
      (node (ref "T1") (pin "3") (pinfunction "C_3") (pintype "passive"))
    )
    (net (code "31") (name "Net-(IC1-VC)") (class "Default")
      (node (ref "IC1") (pin "1") (pinfunction "VC_1") (pintype "passive"))
      (node (ref "R3") (pin "2") (pinfunction "2_2") (pintype "passive"))
    )
    (net (code "32") (name "Net-(IC1-VFB)") (class "Default")
      (node (ref "IC1") (pin "2") (pinfunction "VFB_2") (pintype "passive"))
      (node (ref "R21") (pin "2") (pinfunction "2_2") (pintype "passive"))
      (node (ref "R22") (pin "2") (pinfunction "2_2") (pintype "passive"))
      (node (ref "R23") (pin "2") (pinfunction "2_2") (pintype "passive"))
      (node (ref "R24") (pin "1") (pinfunction "1_1") (pintype "passive"))
      (node (ref "R25") (pin "1") (pinfunction "1_1") (pintype "passive"))
    )
    (net (code "33") (name "Net-(IC1-VSW)") (class "Default")
      (node (ref "C1") (pin "1") (pinfunction "1_1") (pintype "passive"))
      (node (ref "C38") (pin "1") (pinfunction "1_1") (pintype "passive"))
      (node (ref "IC1") (pin "5") (pinfunction "VSW_5") (pintype "output"))
      (node (ref "L2") (pin "2") (pinfunction "2_2") (pintype "passive"))
    )
    (net (code "34") (name "Net-(IC3-CFLY+)") (class "Default")
      (node (ref "C42") (pin "1") (pinfunction "1_1") (pintype "passive"))
      (node (ref "IC3") (pin "5") (pinfunction "CFLY+_5") (pintype "passive"))
    )
    (net (code "35") (name "Net-(IC3-CFLY-)") (class "Default")
      (node (ref "C42") (pin "2") (pinfunction "2_2") (pintype "passive"))
      (node (ref "IC3") (pin "3") (pinfunction "CFLY-_3") (pintype "passive"))
    )
    (net (code "36") (name "Net-(IC3-VO)") (class "Default")
      (node (ref "C44") (pin "1") (pinfunction "1_1") (pintype "passive"))
      (node (ref "IC3") (pin "1") (pinfunction "VO_1") (pintype "power_in"))
      (node (ref "L4") (pin "1") (pinfunction "1_1") (pintype "passive"))
    )
    (net (code "37") (name "Net-(LED1-A)") (class "Default")
      (node (ref "LED1") (pin "1") (pinfunction "A_1") (pintype "passive"))
      (node (ref "R29") (pin "1") (pinfunction "1_1") (pintype "passive"))
    )
    (net (code "38") (name "Net-(OPA1A-+IN)") (class "Default")
      (node (ref "OPA1") (pin "3") (pinfunction "+IN_3") (pintype "input"))
      (node (ref "R11") (pin "2") (pinfunction "2_2") (pintype "passive"))
    )
    (net (code "39") (name "Net-(OPA1A--IN)") (class "Default")
      (node (ref "OPA1") (pin "2") (pinfunction "-IN_2") (pintype "input"))
      (node (ref "R10") (pin "1") (pinfunction "1_1") (pintype "passive"))
      (node (ref "R9") (pin "2") (pinfunction "2_2") (pintype "passive"))
    )
    (net (code "40") (name "Net-(OPA1A-OUT)") (class "Default")
      (node (ref "OPA1") (pin "1") (pinfunction "OUT_1") (pintype "output"))
      (node (ref "R10") (pin "2") (pinfunction "2_2") (pintype "passive"))
      (node (ref "R8") (pin "1") (pinfunction "1_1") (pintype "passive"))
    )
    (net (code "41") (name "Net-(OPA1B-+IN)") (class "Default")
      (node (ref "OPA1") (pin "5") (pinfunction "+IN_5") (pintype "input"))
      (node (ref "R13") (pin "2") (pinfunction "2_2") (pintype "passive"))
    )
    (net (code "42") (name "Net-(OPA1B--IN)") (class "Default")
      (node (ref "OPA1") (pin "6") (pinfunction "-IN_6") (pintype "input"))
      (node (ref "R14") (pin "2") (pinfunction "2_2") (pintype "passive"))
      (node (ref "R15") (pin "1") (pinfunction "1_1") (pintype "passive"))
    )
    (net (code "43") (name "Net-(OPA1B-OUT)") (class "Default")
      (node (ref "OPA1") (pin "7") (pinfunction "OUT_7") (pintype "output"))
      (node (ref "R12") (pin "1") (pinfunction "1_1") (pintype "passive"))
      (node (ref "R15") (pin "2") (pinfunction "2_2") (pintype "passive"))
    )
    (net (code "44") (name "Net-(OPA1C-+IN)") (class "Default")
      (node (ref "OPA1") (pin "10") (pinfunction "+IN_10") (pintype "input"))
      (node (ref "R16") (pin "2") (pinfunction "2_2") (pintype "passive"))
      (node (ref "R17") (pin "2") (pinfunction "2_2") (pintype "passive"))
    )
    (net (code "45") (name "Net-(OPA1C--IN)") (class "Default")
      (node (ref "OPA1") (pin "9") (pinfunction "-IN_9") (pintype "input"))
      (node (ref "R18") (pin "1") (pinfunction "1_1") (pintype "passive"))
      (node (ref "R19") (pin "2") (pinfunction "2_2") (pintype "passive"))
    )
    (net (code "46") (name "Net-(OPA1C-OUT)") (class "Default")
      (node (ref "OPA1") (pin "8") (pinfunction "OUT_8") (pintype "output"))
      (node (ref "R18") (pin "2") (pinfunction "2_2") (pintype "passive"))
      (node (ref "R20") (pin "1") (pinfunction "1_1") (pintype "passive"))
    )
    (net (code "47") (name "Net-(OPA1D-+IN)") (class "Default")
      (node (ref "OPA1") (pin "12") (pinfunction "+IN_12") (pintype "input"))
      (node (ref "R30") (pin "2") (pinfunction "2_2") (pintype "passive"))
      (node (ref "R31") (pin "2") (pinfunction "2_2") (pintype "passive"))
    )
    (net (code "48") (name "Net-(OPA1D--IN)") (class "Default")
      (node (ref "C20") (pin "2") (pinfunction "2_2") (pintype "passive"))
      (node (ref "OPA1") (pin "13") (pinfunction "-IN_13") (pintype "input"))
      (node (ref "R28") (pin "2") (pinfunction "2_2") (pintype "passive"))
    )
    (net (code "49") (name "Net-(OPA1D-OUT)") (class "Default")
      (node (ref "C20") (pin "1") (pinfunction "1_1") (pintype "passive"))
      (node (ref "OPA1") (pin "14") (pinfunction "OUT_14") (pintype "output"))
      (node (ref "R27") (pin "2") (pinfunction "2_2") (pintype "passive"))
    )
    (net (code "50") (name "Net-(REF1-C)") (class "Default")
      (node (ref "C26") (pin "1") (pinfunction "1_1") (pintype "passive"))
      (node (ref "C27") (pin "1") (pinfunction "1_1") (pintype "passive"))
      (node (ref "IC2") (pin "7") (pinfunction "5_7") (pintype "bidirectional"))
      (node (ref "R33") (pin "2") (pinfunction "2_2") (pintype "passive"))
      (node (ref "REF1") (pin "2") (pinfunction "C_2") (pintype "passive"))
    )
    (net (code "51") (name "Net-(T1-B)") (class "Default")
      (node (ref "D4") (pin "A") (pinfunction "A_A") (pintype "passive"))
      (node (ref "R5") (pin "1") (pinfunction "1_1") (pintype "passive"))
      (node (ref "T1") (pin "1") (pinfunction "B_1") (pintype "passive"))
    )
    (net (code "52") (name "Net-(T2-G)") (class "Default")
      (node (ref "D2") (pin "A") (pinfunction "A_A") (pintype "passive"))
      (node (ref "R27") (pin "1") (pinfunction "1_1") (pintype "passive"))
      (node (ref "T2") (pin "1") (pinfunction "G_1") (pintype "bidirectional"))
    )
    (net (code "53") (name "Net-(T2-S)") (class "Default")
      (node (ref "R26") (pin "2") (pinfunction "2_2") (pintype "passive"))
      (node (ref "R28") (pin "1") (pinfunction "1_1") (pintype "passive"))
      (node (ref "T2") (pin "3") (pinfunction "S_3") (pintype "bidirectional"))
    )
    (net (code "54") (name "Net-(T3-D)") (class "Default")
      (node (ref "R42") (pin "1") (pinfunction "1_1") (pintype "passive"))
      (node (ref "T3") (pin "3") (pinfunction "D_3") (pintype "bidirectional"))
    )
    (net (code "55") (name "Net-(T3-S)") (class "Default")
      (node (ref "JP1") (pin "3") (pinfunction "3_3") (pintype "passive"))
      (node (ref "R48") (pin "1") (pinfunction "1_1") (pintype "passive"))
      (node (ref "T3") (pin "2") (pinfunction "S_2") (pintype "bidirectional"))
    )
    (net (code "56") (name "Net-(T4-D)") (class "Default")
      (node (ref "R43") (pin "1") (pinfunction "1_1") (pintype "passive"))
      (node (ref "R44") (pin "1") (pinfunction "1_1") (pintype "passive"))
      (node (ref "T4") (pin "3") (pinfunction "D_3") (pintype "bidirectional"))
    )
    (net (code "57") (name "Net-(T4-S)") (class "Default")
      (node (ref "JP1") (pin "2") (pinfunction "2_2") (pintype "passive"))
      (node (ref "R47") (pin "1") (pinfunction "1_1") (pintype "passive"))
      (node (ref "T4") (pin "2") (pinfunction "S_2") (pintype "bidirectional"))
    )
    (net (code "58") (name "Net-(X3D-P$1)") (class "Default")
      (node (ref "R45") (pin "1") (pinfunction "1_1") (pintype "passive"))
      (node (ref "X3") (pin "4") (pinfunction "P$1_4") (pintype "bidirectional"))
    )
    (net (code "59") (name "Net-(X3E-P$1)") (class "Default")
      (node (ref "R46") (pin "1") (pinfunction "1_1") (pintype "passive"))
      (node (ref "X3") (pin "5") (pinfunction "P$1_5") (pintype "bidirectional"))
    )
    (net (code "60") (name "PGC") (class "Default")
      (node (ref "IC2") (pin "27") (pinfunction "6_27") (pintype "bidirectional"))
      (node (ref "X2") (pin "5") (pinfunction "P$1_5") (pintype "bidirectional"))
    )
    (net (code "61") (name "PGD") (class "Default")
      (node (ref "IC2") (pin "28") (pinfunction "7_28") (pintype "bidirectional"))
      (node (ref "X2") (pin "4") (pinfunction "P$1_4") (pintype "bidirectional"))
    )
    (net (code "62") (name "RXD") (class "Default")
      (node (ref "IC2") (pin "17") (pinfunction "6_17") (pintype "bidirectional"))
      (node (ref "R43") (pin "2") (pinfunction "2_2") (pintype "passive"))
    )
    (net (code "63") (name "SCL") (class "Default")
      (node (ref "IC2") (pin "14") (pinfunction "3_14") (pintype "bidirectional"))
    )
    (net (code "64") (name "SDA") (class "Default")
      (node (ref "IC2") (pin "15") (pinfunction "4_15") (pintype "bidirectional"))
    )
    (net (code "65") (name "TXD") (class "Default")
      (node (ref "IC2") (pin "18") (pinfunction "7_18") (pintype "bidirectional"))
      (node (ref "R42") (pin "2") (pinfunction "2_2") (pintype "passive"))
    )
    (net (code "66") (name "VBAT") (class "Default")
      (node (ref "C39") (pin "1") (pinfunction "1_1") (pintype "passive"))
      (node (ref "C8") (pin "1") (pinfunction "1_1") (pintype "passive"))
      (node (ref "C9") (pin "1") (pinfunction "1_1") (pintype "passive"))
      (node (ref "D1") (pin "C") (pinfunction "C_C") (pintype "passive"))
      (node (ref "R16") (pin "1") (pinfunction "1_1") (pintype "passive"))
      (node (ref "R24") (pin "2") (pinfunction "2_2") (pintype "passive"))
      (node (ref "R25") (pin "2") (pinfunction "2_2") (pintype "passive"))
      (node (ref "T2") (pin "4") (pinfunction "D_4") (pintype "bidirectional"))
      (node (ref "X3") (pin "1") (pinfunction "P$1_1") (pintype "bidirectional"))
      (node (ref "X3") (pin "3") (pinfunction "P$1_3") (pintype "bidirectional"))
    )
    (net (code "67") (name "VBAT_AD") (class "Default")
      (node (ref "C19") (pin "1") (pinfunction "1_1") (pintype "passive"))
      (node (ref "IC2") (pin "3") (pinfunction "1_3") (pintype "bidirectional"))
      (node (ref "R20") (pin "2") (pinfunction "2_2") (pintype "passive"))
    )
    (net (code "68") (name "VCC") (class "Default")
      (node (ref "C41") (pin "1") (pinfunction "1_1") (pintype "passive"))
      (node (ref "C43") (pin "1") (pinfunction "1_1") (pintype "passive"))
      (node (ref "C47") (pin "1") (pinfunction "1_1") (pintype "passive"))
      (node (ref "C5") (pin "1") (pinfunction "1_1") (pintype "passive"))
      (node (ref "D5") (pin "A") (pinfunction "A_A") (pintype "passive"))
      (node (ref "D6") (pin "A") (pinfunction "A_A") (pintype "passive"))
      (node (ref "IC3") (pin "2") (pinfunction "VI_2") (pintype "input"))
      (node (ref "IC4") (pin "3") (pinfunction "VO_3") (pintype "power_in"))
      (node (ref "L5") (pin "1") (pinfunction "1_1") (pintype "passive"))
      (node (ref "R36") (pin "2") (pinfunction "2_2") (pintype "passive"))
      (node (ref "R37") (pin "2") (pinfunction "2_2") (pintype "passive"))
      (node (ref "R39") (pin "2") (pinfunction "2_2") (pintype "passive"))
      (node (ref "R44") (pin "2") (pinfunction "2_2") (pintype "passive"))
    )
    (net (code "69") (name "VDD") (class "Default")
      (node (ref "C11") (pin "1") (pinfunction "1_1") (pintype "passive"))
      (node (ref "C12") (pin "1") (pinfunction "1_1") (pintype "passive"))
      (node (ref "D5") (pin "C") (pinfunction "C_C") (pintype "passive"))
      (node (ref "D7") (pin "C") (pinfunction "C_C") (pintype "passive"))
      (node (ref "IC2") (pin "20") (pinfunction "VDD_20") (pintype "power_in"))
      (node (ref "X2") (pin "2") (pinfunction "P$1_2") (pintype "bidirectional"))
    )
    (net (code "70") (name "VOPA_AD") (class "Default")
      (node (ref "C37") (pin "1") (pinfunction "1_1") (pintype "passive"))
      (node (ref "D3") (pin "C") (pinfunction "C_C") (pintype "passive"))
      (node (ref "IC2") (pin "4") (pinfunction "2_4") (pintype "bidirectional"))
      (node (ref "R49") (pin "1") (pinfunction "1_1") (pintype "passive"))
      (node (ref "R50") (pin "2") (pinfunction "2_2") (pintype "passive"))
    )
    (net (code "71") (name "VP12_AD") (class "Default")
      (node (ref "C21") (pin "1") (pinfunction "1_1") (pintype "passive"))
      (node (ref "D7") (pin "A") (pinfunction "A_A") (pintype "passive"))
      (node (ref "IC2") (pin "5") (pinfunction "3_5") (pintype "bidirectional"))
      (node (ref "R34") (pin "2") (pinfunction "2_2") (pintype "passive"))
      (node (ref "R35") (pin "1") (pinfunction "1_1") (pintype "passive"))
    )
    (net (code "72") (name "VS_CHG") (class "Default")
      (node (ref "C33") (pin "1") (pinfunction "1_1") (pintype "passive"))
      (node (ref "R22") (pin "1") (pinfunction "1_1") (pintype "passive"))
      (node (ref "R23") (pin "1") (pinfunction "1_1") (pintype "passive"))
      (node (ref "R40") (pin "2") (pinfunction "2_2") (pintype "passive"))
    )
    (net (code "73") (name "XEN_CHRG") (class "Default")
      (node (ref "D4") (pin "C") (pinfunction "C_C") (pintype "passive"))
      (node (ref "IC2") (pin "24") (pinfunction "3_24") (pintype "bidirectional"))
    )
    (net (code "74") (name "unconnected-(DAC1A-VOUTB-Pad6)") (class "Default")
      (node (ref "DAC1") (pin "6") (pinfunction "VOUTB_6") (pintype "bidirectional"))
    )
    (net (code "75") (name "unconnected-(F1-P$1-Pad1)") (class "Default")
      (node (ref "F1") (pin "1") (pinfunction "P$1_1") (pintype "passive"))
    )
    (net (code "76") (name "unconnected-(IC2-5-Pad16)") (class "Default")
      (node (ref "IC2") (pin "16") (pinfunction "5_16") (pintype "bidirectional"))
    )
    (net (code "77") (name "unconnected-(X2F-P$1-Pad6)") (class "Default")
      (node (ref "X2") (pin "6") (pinfunction "P$1_6") (pintype "bidirectional"))
    )
    (net (code "78") (name "~{MCLR}") (class "Default")
      (node (ref "IC2") (pin "1") (pinfunction "~{MCLR}_1") (pintype "input"))
      (node (ref "R38") (pin "1") (pinfunction "1_1") (pintype "passive"))
      (node (ref "X2") (pin "1") (pinfunction "P$1_1") (pintype "bidirectional"))
    )
  )
)
